# RPi_Peripheral_HAT.net
KiCad netlist of a schematic drawn in Altium Designer
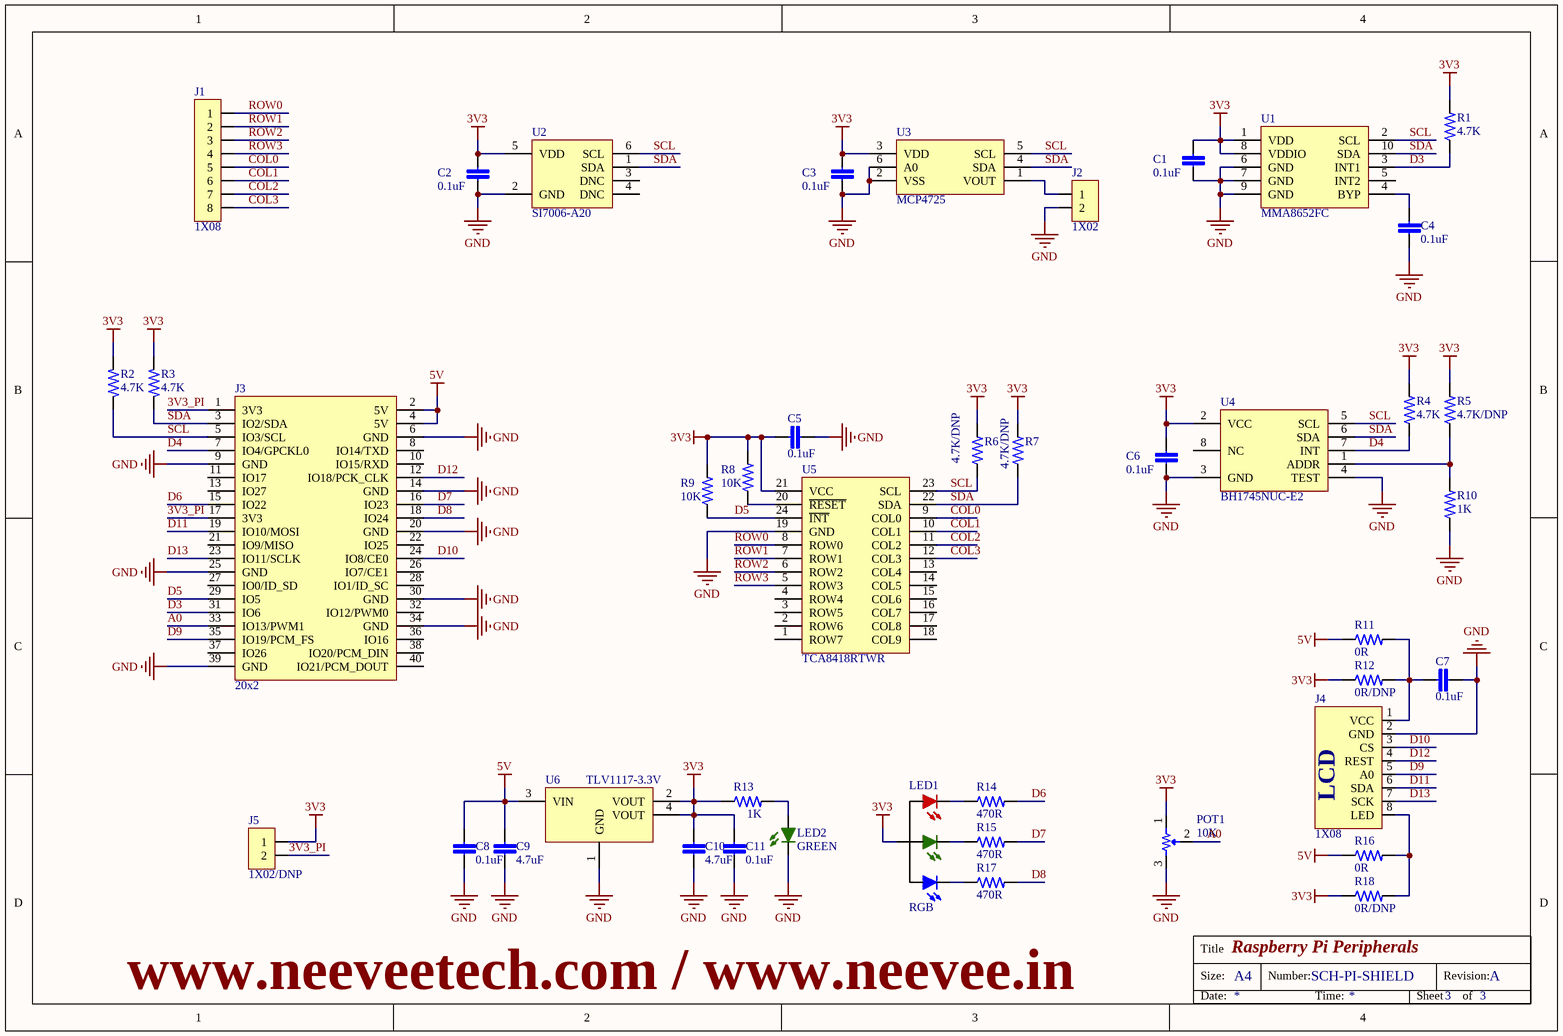
[diagram p0: RPi_Peripheral_HAT.SchDoc]

(export (version "E")
  (design (tool "Eeschema 10.0.6"))
  (components
    (comp (ref "C1")
      (value "0.1uF")
      (footprint "C0603")
      (description "Cap Ceramic 0.1uF 50V X7R 20% SMD 0603 125C T/R")
      (fields
        (field (name "MANUFACTURER") "KEMET")
        (field (name "MANUFACTURER PART NUMBER") "C0603C104M5RACTU")
      )
      (libsource (lib "Schematic_Library") (part "C0603_0.1uF"))
    )
    (comp (ref "C2")
      (value "0.1uF")
      (footprint "C0603")
      (description "Cap Ceramic 0.1uF 50V X7R 20% SMD 0603 125C T/R")
      (fields
        (field (name "MANUFACTURER") "KEMET")
        (field (name "MANUFACTURER PART NUMBER") "C0603C104M5RACTU")
      )
      (libsource (lib "Schematic_Library") (part "C0603_0.1uF"))
    )
    (comp (ref "C3")
      (value "0.1uF")
      (footprint "C0603")
      (description "Cap Ceramic 0.1uF 50V X7R 20% SMD 0603 125C T/R")
      (fields
        (field (name "MANUFACTURER") "KEMET")
        (field (name "MANUFACTURER PART NUMBER") "C0603C104M5RACTU")
      )
      (libsource (lib "Schematic_Library") (part "C0603_0.1uF"))
    )
    (comp (ref "C4")
      (value "0.1uF")
      (footprint "C0603")
      (description "Cap Ceramic 0.1uF 50V X7R 20% SMD 0603 125C T/R")
      (fields
        (field (name "MANUFACTURER") "KEMET")
        (field (name "MANUFACTURER PART NUMBER") "C0603C104M5RACTU")
      )
      (libsource (lib "") (part "C0603_0.1uF_2"))
    )
    (comp (ref "C5")
      (value "0.1uF")
      (footprint "C0603")
      (description "Cap Ceramic 0.1uF 50V X7R 20% SMD 0603 125C T/R")
      (fields
        (field (name "MANUFACTURER") "KEMET")
        (field (name "MANUFACTURER PART NUMBER") "C0603C104M5RACTU")
      )
      (libsource (lib "") (part "C0603_0.1uF_3"))
    )
    (comp (ref "C6")
      (value "0.1uF")
      (footprint "C0603")
      (description "Cap Ceramic 0.1uF 50V X7R 20% SMD 0603 125C T/R")
      (fields
        (field (name "MANUFACTURER") "KEMET")
        (field (name "MANUFACTURER PART NUMBER") "C0603C104M5RACTU")
      )
      (libsource (lib "Schematic_Library") (part "C0603_0.1uF"))
    )
    (comp (ref "C7")
      (value "0.1uF")
      (footprint "C0603")
      (description "Cap Ceramic 0.1uF 50V X7R 20% SMD 0603 125C T/R")
      (fields
        (field (name "MANUFACTURER") "KEMET")
        (field (name "MANUFACTURER PART NUMBER") "C0603C104M5RACTU")
      )
      (libsource (lib "Schematic_Library") (part "C0603_0.1uF"))
    )
    (comp (ref "C8")
      (value "0.1uF")
      (footprint "C0603")
      (description "Cap Ceramic 0.1uF 50V X7R 20% SMD 0603 125C T/R")
      (fields
        (field (name "MANUFACTURER") "KEMET")
        (field (name "MANUFACTURER PART NUMBER") "C0603C104M5RACTU")
      )
      (libsource (lib "") (part "C0603_0.1uF_1"))
    )
    (comp (ref "C9")
      (value "4.7uF")
      (footprint "C0603")
      (description "4.7µF ±10% 10V Ceramic Capacitor X6S 0603 (1608 Metric)")
      (fields
        (field (name "MANUFACTURER") "TDK")
        (field (name "MANUFACTURER PART NUMBER") "C1608X6S1A475K080AC")
      )
      (libsource (lib "Schematic_Library") (part "C0603_4.7uF_10V"))
    )
    (comp (ref "C10")
      (value "4.7uF")
      (footprint "C0603")
      (description "4.7µF ±10% 10V Ceramic Capacitor X6S 0603 (1608 Metric)")
      (fields
        (field (name "MANUFACTURER") "TDK")
        (field (name "MANUFACTURER PART NUMBER") "C1608X6S1A475K080AC")
      )
      (libsource (lib "Schematic_Library") (part "C0603_4.7uF_10V"))
    )
    (comp (ref "C11")
      (value "0.1uF")
      (footprint "C0603")
      (description "Cap Ceramic 0.1uF 50V X7R 20% SMD 0603 125C T/R")
      (fields
        (field (name "MANUFACTURER") "KEMET")
        (field (name "MANUFACTURER PART NUMBER") "C0603C104M5RACTU")
      )
      (libsource (lib "") (part "C0603_0.1uF_1"))
    )
    (comp (ref "J1")
      (value "1X08")
      (footprint "CON_1X08_2.54mm_male_TH")
      (description "Connector Header Through Hole 8 position 0.100\" (2.54mm)")
      (fields
        (field (name "MANUFACTURER") "Amphenol FCI")
        (field (name "MANUFACTURER PART NUMBER") "77311-818-08LF")
      )
      (libsource (lib "Schematic_Library") (part "CON_1X08_2.54mm_male_TH"))
    )
    (comp (ref "J2")
      (value "1X02")
      (footprint "CON_1X02_5MM")
      (description "Wire-To-Board Terminal Block, 5 mm, 2 Ways, 22 AWG, 14 AWG, 1.5 mm, Screw")
      (fields
        (field (name "MANUFACTURER") "Camden Electronics Boss")
        (field (name "MANUFACTURER PART NUMBER") "CTBP5000/2")
      )
      (libsource (lib "Schematic_Library") (part "CON_1X02_5mm"))
    )
    (comp (ref "J3")
      (value "20x2")
      (footprint "RPI_HEADER_2X20_FEMALE")
      (description "GPIO FEMALE HEADER RASPBERRY PI")
      (fields
        (field (name "MANUFACTURER") "Adafruit Industries")
        (field (name "MANUFACTURER PART NUMBER") "2222")
      )
      (libsource (lib "Schematic_Library") (part "RPI_HEADER_20X2_FEMALE"))
    )
    (comp (ref "J4")
      (value "1X08")
      (footprint "CON_1X08_2.54mm_Female_TH")
      (description "Board-To-Board Connector, 2.54 mm, 10 Contacts, Receptacle, 2212S Series, Through Hole, 1 Rows")
      (fields
        (field (name "MANUFACTURER") "Multicomp")
        (field (name "MANUFACTURER PART NUMBER") "2212S-10SG-85")
      )
      (libsource (lib "Schematic_Library") (part "1.44Inch_TFT_LCD_Con"))
    )
    (comp (ref "J5")
      (value "1X02/DNP")
      (footprint "CON_1X02_2.54mm_Male")
      (description "Connector Header Through Hole 2 position 0.100\" (2.54mm)")
      (fields
        (field (name "MANUFACTURER") "Amphenol FCI")
        (field (name "MANUFACTURER PART NUMBER") "77311-818-02LF")
      )
      (libsource (lib "Schematic_Library") (part "CON_1X02_2.54mm_Male"))
    )
    (comp (ref "LED1")
      (value "RGB")
      (footprint "PLCC4")
      (fields
        (field (name "MANUFACTURER") "Broadcom Avago")
        (field (name "MANUFACTURER PART NUMBER") "ASMB-MTB0-0A3A2")
      )
      (libsource (lib "Schematic_Library") (part "LED_RGB"))
    )
    (comp (ref "LED2")
      (value "GREEN")
      (footprint "LED_0805_GREEN")
      (description "KP-2012LCGCK -  LED, Low Power, Green, SMD, 0805, 2 mA, 1.9 V, 570 nm")
      (fields
        (field (name "MANUFACTURER") "Kingbright")
        (field (name "MANUFACTURER PART NUMBER") "KP-2012LCGCK")
      )
      (libsource (lib "Schematic_Library") (part "LED0805_GREEN"))
    )
    (comp (ref "POT1")
      (value "10K")
      (footprint "PTV09A_POTENTIOMETER")
      (fields
        (field (name "MANUFACTURER") "Bourns")
        (field (name "MANUFACTURER PART NUMBER") "PTV09A-4015U-B103")
        (field (name "TOLERANCE") "20%")
      )
      (libsource (lib "Schematic_Library") (part "PTV09A-4015U-B103"))
    )
    (comp (ref "R1")
      (value "4.7K")
      (footprint "R0603")
      (description "SMD Chip Resistor, 0603 [1608 Metric], 4.7 kohm, MCWR Series, 75 V, Thick Film, 100 mW")
      (fields
        (field (name "MANUFACTURER") "Multicomp")
        (field (name "MANUFACTURER PART NUMBER") "MCWR06X4701FTL")
      )
      (libsource (lib "Schematic_Library") (part "R0603_4.7K"))
    )
    (comp (ref "R2")
      (value "4.7K")
      (footprint "R0603")
      (description "SMD Chip Resistor, 0603 [1608 Metric], 4.7 kohm, MCWR Series, 75 V, Thick Film, 100 mW")
      (fields
        (field (name "MANUFACTURER") "Multicomp")
        (field (name "MANUFACTURER PART NUMBER") "MCWR06X4701FTL")
      )
      (libsource (lib "Schematic_Library") (part "R0603_4.7K"))
    )
    (comp (ref "R3")
      (value "4.7K")
      (footprint "R0603")
      (description "SMD Chip Resistor, 0603 [1608 Metric], 4.7 kohm, MCWR Series, 75 V, Thick Film, 100 mW")
      (fields
        (field (name "MANUFACTURER") "Multicomp")
        (field (name "MANUFACTURER PART NUMBER") "MCWR06X4701FTL")
      )
      (libsource (lib "Schematic_Library") (part "R0603_4.7K"))
    )
    (comp (ref "R4")
      (value "4.7K")
      (footprint "R0603")
      (description "SMD Chip Resistor, 0603 [1608 Metric], 4.7 kohm, MCWR Series, 75 V, Thick Film, 100 mW")
      (fields
        (field (name "MANUFACTURER") "Multicomp")
        (field (name "MANUFACTURER PART NUMBER") "MCWR06X4701FTL")
      )
      (libsource (lib "Schematic_Library") (part "R0603_4.7K"))
    )
    (comp (ref "R5")
      (value "4.7K/DNP")
      (footprint "R0603")
      (description "SMD Chip Resistor, 0603 [1608 Metric], 4.7 kohm, MCWR Series, 75 V, Thick Film, 100 mW (DNP)")
      (fields
        (field (name "MANUFACTURER") "Multicomp")
        (field (name "MANUFACTURER PART NUMBER") "MCWR06X4701FTL")
      )
      (libsource (lib "Schematic_Library") (part "R0603_4.7K/DNP"))
    )
    (comp (ref "R6")
      (value "4.7K/DNP")
      (footprint "R0603")
      (description "SMD Chip Resistor, 0603 [1608 Metric], 4.7 kohm, MCWR Series, 75 V, Thick Film, 100 mW (DNP)")
      (fields
        (field (name "MANUFACTURER") "Multicomp")
        (field (name "MANUFACTURER PART NUMBER") "MCWR06X4701FTL")
      )
      (libsource (lib "Schematic_Library") (part "R0603_4.7K/DNP"))
    )
    (comp (ref "R7")
      (value "4.7K/DNP")
      (footprint "R0603")
      (description "SMD Chip Resistor, 0603 [1608 Metric], 4.7 kohm, MCWR Series, 75 V, Thick Film, 100 mW (DNP)")
      (fields
        (field (name "MANUFACTURER") "Multicomp")
        (field (name "MANUFACTURER PART NUMBER") "MCWR06X4701FTL")
      )
      (libsource (lib "Schematic_Library") (part "R0603_4.7K/DNP"))
    )
    (comp (ref "R8")
      (value "10K")
      (footprint "R0603")
      (description "SMD Chip Resistor, 0603 [1608 Metric], 10 kohm, MCWR Series, 75 V, Thick Film, 100 mW")
      (fields
        (field (name "MANUFACTURER") "Multicomp")
        (field (name "MANUFACTURER PART NUMBER") "MCWR06X1002FTL")
      )
      (libsource (lib "Schematic_Library") (part "R0603_10K"))
    )
    (comp (ref "R9")
      (value "10K")
      (footprint "R0603")
      (description "SMD Chip Resistor, 0603 [1608 Metric], 10 kohm, MCWR Series, 75 V, Thick Film, 100 mW")
      (fields
        (field (name "MANUFACTURER") "Multicomp")
        (field (name "MANUFACTURER PART NUMBER") "MCWR06X1002FTL")
      )
      (libsource (lib "Schematic_Library") (part "R0603_10K"))
    )
    (comp (ref "R10")
      (value "1K")
      (footprint "R0603")
      (description "SMD Chip Resistor, 0603 [1608 Metric], 1 kohm, MCWR Series, 75 V, Thick Film, 100 mW")
      (fields
        (field (name "MANUFACTURER") "Multicomp")
        (field (name "MANUFACTURER PART NUMBER") "MCWR06X1001FTL")
      )
      (libsource (lib "Schematic_Library") (part "R0603_1K"))
    )
    (comp (ref "R11")
      (value "0R")
      (footprint "R0603")
      (description "SMD Chip Resistor, Jumper, 0603 [1608 Metric], 0 ohm, MCWR Series, 75 V, Thick Film, 100 mW")
      (fields
        (field (name "MANUFACTURER") "Multicomp")
        (field (name "MANUFACTURER PART NUMBER") "MCWR06X000PTL")
      )
      (libsource (lib "Schematic_Library") (part "R0603_0R"))
    )
    (comp (ref "R12")
      (value "0R/DNP")
      (footprint "R0603")
      (description "SMD Chip Resistor, Jumper, 0603 [1608 Metric], 0 ohm, MCWR Series, 75 V, Thick Film, 100 mW (DNP)")
      (fields
        (field (name "MANUFACTURER") "Multicomp")
        (field (name "MANUFACTURER PART NUMBER") "MCWR06X000PTL")
      )
      (libsource (lib "Schematic_Library") (part "R0603_0R_DNP"))
    )
    (comp (ref "R13")
      (value "1K")
      (footprint "R0603")
      (description "SMD Chip Resistor, 0603 [1608 Metric], 1 kohm, MCWR Series, 75 V, Thick Film, 100 mW")
      (fields
        (field (name "MANUFACTURER") "Multicomp")
        (field (name "MANUFACTURER PART NUMBER") "MCWR06X1001FTL")
      )
      (libsource (lib "Schematic_Library") (part "R0603_1K"))
    )
    (comp (ref "R14")
      (value "470R")
      (footprint "R0603")
      (description "SMD Chip Resistor, 0603 [1608 Metric], 470 ohm, MCWR Series, 75 V, Thick Film, 100 mW")
      (fields
        (field (name "MANUFACTURER") "Multicomp")
        (field (name "MANUFACTURER PART NUMBER") "MCWR06X4700FTL")
      )
      (libsource (lib "Schematic_Library") (part "R0603_470R"))
    )
    (comp (ref "R15")
      (value "470R")
      (footprint "R0603")
      (description "SMD Chip Resistor, 0603 [1608 Metric], 470 ohm, MCWR Series, 75 V, Thick Film, 100 mW")
      (fields
        (field (name "MANUFACTURER") "Multicomp")
        (field (name "MANUFACTURER PART NUMBER") "MCWR06X4700FTL")
      )
      (libsource (lib "Schematic_Library") (part "R0603_470R"))
    )
    (comp (ref "R16")
      (value "0R")
      (footprint "R0603")
      (description "SMD Chip Resistor, Jumper, 0603 [1608 Metric], 0 ohm, MCWR Series, 75 V, Thick Film, 100 mW")
      (fields
        (field (name "MANUFACTURER") "Multicomp")
        (field (name "MANUFACTURER PART NUMBER") "MCWR06X000PTL")
      )
      (libsource (lib "Schematic_Library") (part "R0603_0R"))
    )
    (comp (ref "R17")
      (value "470R")
      (footprint "R0603")
      (description "SMD Chip Resistor, 0603 [1608 Metric], 470 ohm, MCWR Series, 75 V, Thick Film, 100 mW")
      (fields
        (field (name "MANUFACTURER") "Multicomp")
        (field (name "MANUFACTURER PART NUMBER") "MCWR06X4700FTL")
      )
      (libsource (lib "Schematic_Library") (part "R0603_470R"))
    )
    (comp (ref "R18")
      (value "0R/DNP")
      (footprint "R0603")
      (description "SMD Chip Resistor, Jumper, 0603 [1608 Metric], 0 ohm, MCWR Series, 75 V, Thick Film, 100 mW (DNP)")
      (fields
        (field (name "MANUFACTURER") "Multicomp")
        (field (name "MANUFACTURER PART NUMBER") "MCWR06X000PTL")
      )
      (libsource (lib "Schematic_Library") (part "R0603_0R_DNP"))
    )
    (comp (ref "U1")
      (value "MMA8652FC")
      (footprint "DFN10")
      (description "Accelerometer X, Y, Z Axis ±2g, 4g, 8g 0.78Hz ~ 400Hz 10-DFN (2x2)")
      (fields
        (field (name "MANUFACTURER") "NXP Freescale")
        (field (name "MANUFACTURER PART NUMBER") "MMA8652FCR1")
      )
      (libsource (lib "Schematic_Library") (part "MMA8652FC"))
    )
    (comp (ref "U2")
      (value "SI7006-A20")
      (footprint "DFN6")
      (description "Humidity Temperature Sensor 0 ~ 100% RH I²C ±5% RH 18s Surface Mount")
      (fields
        (field (name "MANUFACTURER") "Silicon Labs")
        (field (name "MANUFACTURER PART NUMBER") "SI7006-A20-IM")
      )
      (libsource (lib "Schematic_Library") (part "SI7006-A20-IM"))
    )
    (comp (ref "U3")
      (value "MCP4725")
      (footprint "SOT23-6")
      (description "12 Bit Digital to Analog Converter 1 SOT-23-6")
      (fields
        (field (name "MANUFACTURER") "Microchip")
        (field (name "MANUFACTURER PART NUMBER") "MCP4725A2T-E/CH")
      )
      (libsource (lib "Schematic_Library") (part "MCP4725"))
    )
    (comp (ref "U4")
      (value "BH1745NUC-E2")
      (footprint "DFN8")
      (description "ROHM - BH1745NUC-E2 - Colour Sensor, 16 Bit, I2C, Serial Output, 2.3 V to 3.6 V, WSON-8")
      (fields (field (name "MANUFACTURER") "Rohm"))
      (libsource (lib "Schematic_Library") (part "BH1745NUC-E2"))
    )
    (comp (ref "U5")
      (value "TCA8418RTWR")
      (footprint "QFN24-0.5mm")
      (description "TCA8418 I2C Controlled Keypad Scan IC With Integrated ESD Protection")
      (fields (field (name "MANUFACTURER") "Texas Instruments"))
      (libsource (lib "Schematic_Library") (part "TCA8418RTWR"))
    )
    (comp (ref "U6")
      (value "TLV1117-3.3V")
      (footprint "SOT223")
      (description "Fixed LDO Voltage Regulator, 2V to 5.5V, 455mV Dropout, 3.3Vout, 1Aout, SOT-223-4")
      (fields
        (field (name "MANUFACTURER") "Texas Instruments")
        (field (name "MANUFACTURER PART NUMBER") "TLV1117LV33DCYR")
      )
      (libsource (lib "Schematic_Library") (part "TLV1117LV33"))
    )
  )
  (nets
    (net (code "1") (name "/3V3_PI") (class "Default")
      (node (ref "J3") (pin "1") (pinfunction "3V3_1") (pintype "passive"))
      (node (ref "J3") (pin "17") (pinfunction "3V3_17") (pintype "passive"))
      (node (ref "J5") (pin "2") (pinfunction "2_2") (pintype "passive"))
    )
    (net (code "2") (name "/A0") (class "Default")
      (node (ref "J3") (pin "33") (pinfunction "IO13/PWM1_33") (pintype "passive"))
      (node (ref "POT1") (pin "2") (pinfunction "2_2") (pintype "passive"))
    )
    (net (code "3") (name "/COL0") (class "Default")
      (node (ref "J1") (pin "5") (pinfunction "5_5") (pintype "passive"))
      (node (ref "U5") (pin "9") (pinfunction "COL0_9") (pintype "passive"))
    )
    (net (code "4") (name "/COL1") (class "Default")
      (node (ref "J1") (pin "6") (pinfunction "6_6") (pintype "passive"))
      (node (ref "U5") (pin "10") (pinfunction "COL1_10") (pintype "passive"))
    )
    (net (code "5") (name "/COL2") (class "Default")
      (node (ref "J1") (pin "7") (pinfunction "7_7") (pintype "passive"))
      (node (ref "U5") (pin "11") (pinfunction "COL2_11") (pintype "passive"))
    )
    (net (code "6") (name "/COL3") (class "Default")
      (node (ref "J1") (pin "8") (pinfunction "8_8") (pintype "passive"))
      (node (ref "U5") (pin "12") (pinfunction "COL3_12") (pintype "passive"))
    )
    (net (code "7") (name "/D3") (class "Default")
      (node (ref "J3") (pin "31") (pinfunction "IO6_31") (pintype "passive"))
      (node (ref "R1") (pin "1") (pinfunction "1_1") (pintype "passive"))
      (node (ref "U1") (pin "3") (pinfunction "INT1_3") (pintype "passive"))
    )
    (net (code "8") (name "/D4") (class "Default")
      (node (ref "J3") (pin "7") (pinfunction "IO4/GPCKL0_7") (pintype "passive"))
      (node (ref "R4") (pin "1") (pinfunction "1_1") (pintype "passive"))
      (node (ref "U4") (pin "7") (pinfunction "INT_7") (pintype "passive"))
    )
    (net (code "9") (name "/D5") (class "Default")
      (node (ref "J3") (pin "29") (pinfunction "IO5_29") (pintype "passive"))
      (node (ref "R9") (pin "1") (pinfunction "1_1") (pintype "passive"))
      (node (ref "U5") (pin "24") (pinfunction "~{INT}_24") (pintype "passive"))
    )
    (net (code "10") (name "/D6") (class "Default")
      (node (ref "J3") (pin "15") (pinfunction "IO22_15") (pintype "passive"))
      (node (ref "R14") (pin "2") (pinfunction "2_2") (pintype "passive"))
    )
    (net (code "11") (name "/D7") (class "Default")
      (node (ref "J3") (pin "16") (pinfunction "IO23_16") (pintype "passive"))
      (node (ref "R15") (pin "2") (pinfunction "2_2") (pintype "passive"))
    )
    (net (code "12") (name "/D8") (class "Default")
      (node (ref "J3") (pin "18") (pinfunction "IO24_18") (pintype "passive"))
      (node (ref "R17") (pin "2") (pinfunction "2_2") (pintype "passive"))
    )
    (net (code "13") (name "/D9") (class "Default")
      (node (ref "J3") (pin "35") (pinfunction "IO19/PCM_FS_35") (pintype "passive"))
      (node (ref "J4") (pin "5") (pinfunction "A0_5") (pintype "passive"))
    )
    (net (code "14") (name "/D10") (class "Default")
      (node (ref "J3") (pin "24") (pinfunction "IO8/CE0_24") (pintype "passive"))
      (node (ref "J4") (pin "3") (pinfunction "CS_3") (pintype "passive"))
    )
    (net (code "15") (name "/D11") (class "Default")
      (node (ref "J3") (pin "19") (pinfunction "IO10/MOSI_19") (pintype "passive"))
      (node (ref "J4") (pin "6") (pinfunction "SDA_6") (pintype "passive"))
    )
    (net (code "16") (name "/D12") (class "Default")
      (node (ref "J3") (pin "12") (pinfunction "IO18/PCK_CLK_12") (pintype "passive"))
      (node (ref "J4") (pin "4") (pinfunction "REST_4") (pintype "passive"))
    )
    (net (code "17") (name "/D13") (class "Default")
      (node (ref "J3") (pin "23") (pinfunction "IO11/SCLK_23") (pintype "passive"))
      (node (ref "J4") (pin "7") (pinfunction "SCK_7") (pintype "passive"))
    )
    (net (code "18") (name "/ROW0") (class "Default")
      (node (ref "J1") (pin "1") (pinfunction "1_1") (pintype "passive"))
      (node (ref "U5") (pin "8") (pinfunction "ROW0_8") (pintype "passive"))
    )
    (net (code "19") (name "/ROW1") (class "Default")
      (node (ref "J1") (pin "2") (pinfunction "2_2") (pintype "passive"))
      (node (ref "U5") (pin "7") (pinfunction "ROW1_7") (pintype "passive"))
    )
    (net (code "20") (name "/ROW2") (class "Default")
      (node (ref "J1") (pin "3") (pinfunction "3_3") (pintype "passive"))
      (node (ref "U5") (pin "6") (pinfunction "ROW2_6") (pintype "passive"))
    )
    (net (code "21") (name "/ROW3") (class "Default")
      (node (ref "J1") (pin "4") (pinfunction "4_4") (pintype "passive"))
      (node (ref "U5") (pin "5") (pinfunction "ROW3_5") (pintype "passive"))
    )
    (net (code "22") (name "/SCL") (class "Default")
      (node (ref "J3") (pin "5") (pinfunction "IO3/SCL_5") (pintype "passive"))
      (node (ref "R2") (pin "1") (pinfunction "1_1") (pintype "passive"))
      (node (ref "R6") (pin "1") (pinfunction "1_1") (pintype "passive"))
      (node (ref "U1") (pin "2") (pinfunction "SCL_2") (pintype "passive"))
      (node (ref "U2") (pin "6") (pinfunction "SCL_6") (pintype "passive"))
      (node (ref "U3") (pin "5") (pinfunction "SCL_5") (pintype "passive"))
      (node (ref "U4") (pin "5") (pinfunction "SCL_5") (pintype "passive"))
      (node (ref "U5") (pin "23") (pinfunction "SCL_23") (pintype "passive"))
    )
    (net (code "23") (name "/SDA") (class "Default")
      (node (ref "J3") (pin "3") (pinfunction "IO2/SDA_3") (pintype "passive"))
      (node (ref "R3") (pin "1") (pinfunction "1_1") (pintype "passive"))
      (node (ref "R7") (pin "1") (pinfunction "1_1") (pintype "passive"))
      (node (ref "U1") (pin "10") (pinfunction "SDA_10") (pintype "passive"))
      (node (ref "U2") (pin "1") (pinfunction "SDA_1") (pintype "passive"))
      (node (ref "U3") (pin "4") (pinfunction "SDA_4") (pintype "passive"))
      (node (ref "U4") (pin "6") (pinfunction "SDA_6") (pintype "passive"))
      (node (ref "U5") (pin "22") (pinfunction "SDA_22") (pintype "passive"))
    )
    (net (code "24") (name "3V3") (class "Default")
      (node (ref "C1") (pin "2") (pinfunction "2_2") (pintype "passive"))
      (node (ref "C10") (pin "1") (pinfunction "1_1") (pintype "passive"))
      (node (ref "C11") (pin "2") (pinfunction "2_2") (pintype "passive"))
      (node (ref "C2") (pin "2") (pinfunction "2_2") (pintype "passive"))
      (node (ref "C3") (pin "2") (pinfunction "2_2") (pintype "passive"))
      (node (ref "C5") (pin "2") (pinfunction "2_2") (pintype "passive"))
      (node (ref "C6") (pin "2") (pinfunction "2_2") (pintype "passive"))
      (node (ref "J5") (pin "1") (pinfunction "1_1") (pintype "passive"))
      (node (ref "LED1") (pin "1") (pinfunction "CA_1") (pintype "passive"))
      (node (ref "POT1") (pin "1") (pinfunction "1_1") (pintype "passive"))
      (node (ref "R1") (pin "2") (pinfunction "2_2") (pintype "passive"))
      (node (ref "R12") (pin "1") (pinfunction "1_1") (pintype "passive"))
      (node (ref "R13") (pin "1") (pinfunction "1_1") (pintype "passive"))
      (node (ref "R18") (pin "1") (pinfunction "1_1") (pintype "passive"))
      (node (ref "R2") (pin "2") (pinfunction "2_2") (pintype "passive"))
      (node (ref "R3") (pin "2") (pinfunction "2_2") (pintype "passive"))
      (node (ref "R4") (pin "2") (pinfunction "2_2") (pintype "passive"))
      (node (ref "R5") (pin "2") (pinfunction "2_2") (pintype "passive"))
      (node (ref "R6") (pin "2") (pinfunction "2_2") (pintype "passive"))
      (node (ref "R7") (pin "2") (pinfunction "2_2") (pintype "passive"))
      (node (ref "R8") (pin "2") (pinfunction "2_2") (pintype "passive"))
      (node (ref "R9") (pin "2") (pinfunction "2_2") (pintype "passive"))
      (node (ref "U1") (pin "1") (pinfunction "VDD_1") (pintype "passive"))
      (node (ref "U1") (pin "8") (pinfunction "VDDIO_8") (pintype "passive"))
      (node (ref "U2") (pin "5") (pinfunction "VDD_5") (pintype "passive"))
      (node (ref "U3") (pin "3") (pinfunction "VDD_3") (pintype "passive"))
      (node (ref "U4") (pin "2") (pinfunction "VCC_2") (pintype "passive"))
      (node (ref "U5") (pin "21") (pinfunction "VCC_21") (pintype "passive"))
      (node (ref "U6") (pin "2") (pinfunction "VOUT_2") (pintype "passive"))
      (node (ref "U6") (pin "4") (pinfunction "VOUT_4") (pintype "passive"))
    )
    (net (code "25") (name "5V") (class "Default")
      (node (ref "C8") (pin "2") (pinfunction "2_2") (pintype "passive"))
      (node (ref "C9") (pin "1") (pinfunction "1_1") (pintype "passive"))
      (node (ref "J3") (pin "2") (pinfunction "5V_2") (pintype "passive"))
      (node (ref "J3") (pin "4") (pinfunction "5V_4") (pintype "passive"))
      (node (ref "R11") (pin "1") (pinfunction "1_1") (pintype "passive"))
      (node (ref "R16") (pin "1") (pinfunction "1_1") (pintype "passive"))
      (node (ref "U6") (pin "3") (pinfunction "VIN_3") (pintype "passive"))
    )
    (net (code "26") (name "GND") (class "Default")
      (node (ref "C1") (pin "1") (pinfunction "1_1") (pintype "passive"))
      (node (ref "C10") (pin "2") (pinfunction "2_2") (pintype "passive"))
      (node (ref "C11") (pin "1") (pinfunction "1_1") (pintype "passive"))
      (node (ref "C2") (pin "1") (pinfunction "1_1") (pintype "passive"))
      (node (ref "C3") (pin "1") (pinfunction "1_1") (pintype "passive"))
      (node (ref "C4") (pin "2") (pinfunction "2_2") (pintype "passive"))
      (node (ref "C5") (pin "1") (pinfunction "1_1") (pintype "passive"))
      (node (ref "C6") (pin "1") (pinfunction "1_1") (pintype "passive"))
      (node (ref "C7") (pin "2") (pinfunction "2_2") (pintype "passive"))
      (node (ref "C8") (pin "1") (pinfunction "1_1") (pintype "passive"))
      (node (ref "C9") (pin "2") (pinfunction "2_2") (pintype "passive"))
      (node (ref "J2") (pin "2") (pinfunction "2_2") (pintype "passive"))
      (node (ref "J3") (pin "14") (pinfunction "GND_14") (pintype "passive"))
      (node (ref "J3") (pin "20") (pinfunction "GND_20") (pintype "passive"))
      (node (ref "J3") (pin "25") (pinfunction "GND_25") (pintype "passive"))
      (node (ref "J3") (pin "30") (pinfunction "GND_30") (pintype "passive"))
      (node (ref "J3") (pin "34") (pinfunction "GND_34") (pintype "passive"))
      (node (ref "J3") (pin "39") (pinfunction "GND_39") (pintype "passive"))
      (node (ref "J3") (pin "6") (pinfunction "GND_6") (pintype "passive"))
      (node (ref "J3") (pin "9") (pinfunction "GND_9") (pintype "passive"))
      (node (ref "J4") (pin "2") (pinfunction "GND_2") (pintype "passive"))
      (node (ref "LED2") (pin "C") (pinfunction "C_C") (pintype "passive"))
      (node (ref "POT1") (pin "3") (pinfunction "3_3") (pintype "passive"))
      (node (ref "R10") (pin "1") (pinfunction "1_1") (pintype "passive"))
      (node (ref "U1") (pin "6") (pinfunction "GND_6") (pintype "passive"))
      (node (ref "U1") (pin "7") (pinfunction "GND_7") (pintype "passive"))
      (node (ref "U1") (pin "9") (pinfunction "GND_9") (pintype "passive"))
      (node (ref "U2") (pin "2") (pinfunction "GND_2") (pintype "passive"))
      (node (ref "U3") (pin "2") (pinfunction "VSS_2") (pintype "passive"))
      (node (ref "U3") (pin "6") (pinfunction "A0_6") (pintype "passive"))
      (node (ref "U4") (pin "3") (pinfunction "GND_3") (pintype "passive"))
      (node (ref "U4") (pin "4") (pinfunction "TEST_4") (pintype "passive"))
      (node (ref "U5") (pin "19") (pinfunction "GND_19") (pintype "passive"))
      (node (ref "U6") (pin "1") (pinfunction "GND_1") (pintype "passive"))
    )
    (net (code "27") (name "Net-(J4-LED)") (class "Default")
      (node (ref "J4") (pin "8") (pinfunction "LED_8") (pintype "passive"))
      (node (ref "R16") (pin "2") (pinfunction "2_2") (pintype "passive"))
      (node (ref "R18") (pin "2") (pinfunction "2_2") (pintype "passive"))
    )
    (net (code "28") (name "Net-(J4-VCC)") (class "Default")
      (node (ref "C7") (pin "1") (pinfunction "1_1") (pintype "passive"))
      (node (ref "J4") (pin "1") (pinfunction "VCC_1") (pintype "passive"))
      (node (ref "R11") (pin "2") (pinfunction "2_2") (pintype "passive"))
      (node (ref "R12") (pin "2") (pinfunction "2_2") (pintype "passive"))
    )
    (net (code "29") (name "Net-(LED1-BLUE)") (class "Default")
      (node (ref "LED1") (pin "2") (pinfunction "BLUE_2") (pintype "passive"))
      (node (ref "R17") (pin "1") (pinfunction "1_1") (pintype "passive"))
    )
    (net (code "30") (name "Net-(LED1-GREEN)") (class "Default")
      (node (ref "LED1") (pin "3") (pinfunction "GREEN_3") (pintype "passive"))
      (node (ref "R15") (pin "1") (pinfunction "1_1") (pintype "passive"))
    )
    (net (code "31") (name "Net-(LED1-RED)") (class "Default")
      (node (ref "LED1") (pin "4") (pinfunction "RED_4") (pintype "passive"))
      (node (ref "R14") (pin "1") (pinfunction "1_1") (pintype "passive"))
    )
    (net (code "32") (name "Net-(LED2-PadA)") (class "Default")
      (node (ref "LED2") (pin "A") (pinfunction "A_A") (pintype "passive"))
      (node (ref "R13") (pin "2") (pinfunction "2_2") (pintype "passive"))
    )
    (net (code "33") (name "Net-(U1-BYP)") (class "Default")
      (node (ref "C4") (pin "1") (pinfunction "1_1") (pintype "passive"))
      (node (ref "U1") (pin "4") (pinfunction "BYP_4") (pintype "passive"))
    )
    (net (code "34") (name "Net-(U3-VOUT)") (class "Default")
      (node (ref "J2") (pin "1") (pinfunction "1_1") (pintype "passive"))
      (node (ref "U3") (pin "1") (pinfunction "VOUT_1") (pintype "passive"))
    )
    (net (code "35") (name "Net-(U4-ADDR)") (class "Default")
      (node (ref "R10") (pin "2") (pinfunction "2_2") (pintype "passive"))
      (node (ref "R5") (pin "1") (pinfunction "1_1") (pintype "passive"))
      (node (ref "U4") (pin "1") (pinfunction "ADDR_1") (pintype "passive"))
    )
    (net (code "36") (name "Net-(U5-~{RESET})") (class "Default")
      (node (ref "R8") (pin "1") (pinfunction "1_1") (pintype "passive"))
      (node (ref "U5") (pin "20") (pinfunction "~{RESET}_20") (pintype "passive"))
    )
    (net (code "37") (name "unconnected-(J3-IO0{slash}ID_SD-Pad27)") (class "Default")
      (node (ref "J3") (pin "27") (pinfunction "IO0/ID_SD_27") (pintype "passive"))
    )
    (net (code "38") (name "unconnected-(J3-IO1{slash}ID_SC-Pad28)") (class "Default")
      (node (ref "J3") (pin "28") (pinfunction "IO1/ID_SC_28") (pintype "passive"))
    )
    (net (code "39") (name "unconnected-(J3-IO7{slash}CE1-Pad26)") (class "Default")
      (node (ref "J3") (pin "26") (pinfunction "IO7/CE1_26") (pintype "passive"))
    )
    (net (code "40") (name "unconnected-(J3-IO9{slash}MISO-Pad21)") (class "Default")
      (node (ref "J3") (pin "21") (pinfunction "IO9/MISO_21") (pintype "passive"))
    )
    (net (code "41") (name "unconnected-(J3-IO12{slash}PWM0-Pad32)") (class "Default")
      (node (ref "J3") (pin "32") (pinfunction "IO12/PWM0_32") (pintype "passive"))
    )
    (net (code "42") (name "unconnected-(J3-IO14{slash}TXD-Pad8)") (class "Default")
      (node (ref "J3") (pin "8") (pinfunction "IO14/TXD_8") (pintype "passive"))
    )
    (net (code "43") (name "unconnected-(J3-IO15{slash}RXD-Pad10)") (class "Default")
      (node (ref "J3") (pin "10") (pinfunction "IO15/RXD_10") (pintype "passive"))
    )
    (net (code "44") (name "unconnected-(J3-IO16-Pad36)") (class "Default")
      (node (ref "J3") (pin "36") (pinfunction "IO16_36") (pintype "passive"))
    )
    (net (code "45") (name "unconnected-(J3-IO17-Pad11)") (class "Default")
      (node (ref "J3") (pin "11") (pinfunction "IO17_11") (pintype "passive"))
    )
    (net (code "46") (name "unconnected-(J3-IO20{slash}PCM_DIN-Pad38)") (class "Default")
      (node (ref "J3") (pin "38") (pinfunction "IO20/PCM_DIN_38") (pintype "passive"))
    )
    (net (code "47") (name "unconnected-(J3-IO21{slash}PCM_DOUT-Pad40)") (class "Default")
      (node (ref "J3") (pin "40") (pinfunction "IO21/PCM_DOUT_40") (pintype "passive"))
    )
    (net (code "48") (name "unconnected-(J3-IO25-Pad22)") (class "Default")
      (node (ref "J3") (pin "22") (pinfunction "IO25_22") (pintype "passive"))
    )
    (net (code "49") (name "unconnected-(J3-IO26-Pad37)") (class "Default")
      (node (ref "J3") (pin "37") (pinfunction "IO26_37") (pintype "passive"))
    )
    (net (code "50") (name "unconnected-(J3-IO27-Pad13)") (class "Default")
      (node (ref "J3") (pin "13") (pinfunction "IO27_13") (pintype "passive"))
    )
    (net (code "51") (name "unconnected-(U1-INT2-Pad5)") (class "Default")
      (node (ref "U1") (pin "5") (pinfunction "INT2_5") (pintype "passive"))
    )
    (net (code "52") (name "unconnected-(U2-DNC-Pad3)") (class "Default")
      (node (ref "U2") (pin "3") (pinfunction "DNC_3") (pintype "passive"))
    )
    (net (code "53") (name "unconnected-(U2-DNC-Pad4)") (class "Default")
      (node (ref "U2") (pin "4") (pinfunction "DNC_4") (pintype "passive"))
    )
    (net (code "54") (name "unconnected-(U4-NC-Pad8)") (class "Default")
      (node (ref "U4") (pin "8") (pinfunction "NC_8") (pintype "passive"))
    )
    (net (code "55") (name "unconnected-(U5-COL4-Pad13)") (class "Default")
      (node (ref "U5") (pin "13") (pinfunction "COL4_13") (pintype "passive"))
    )
    (net (code "56") (name "unconnected-(U5-COL5-Pad14)") (class "Default")
      (node (ref "U5") (pin "14") (pinfunction "COL5_14") (pintype "passive"))
    )
    (net (code "57") (name "unconnected-(U5-COL6-Pad15)") (class "Default")
      (node (ref "U5") (pin "15") (pinfunction "COL6_15") (pintype "passive"))
    )
    (net (code "58") (name "unconnected-(U5-COL7-Pad16)") (class "Default")
      (node (ref "U5") (pin "16") (pinfunction "COL7_16") (pintype "passive"))
    )
    (net (code "59") (name "unconnected-(U5-COL8-Pad17)") (class "Default")
      (node (ref "U5") (pin "17") (pinfunction "COL8_17") (pintype "passive"))
    )
    (net (code "60") (name "unconnected-(U5-COL9-Pad18)") (class "Default")
      (node (ref "U5") (pin "18") (pinfunction "COL9_18") (pintype "passive"))
    )
    (net (code "61") (name "unconnected-(U5-ROW4-Pad4)") (class "Default")
      (node (ref "U5") (pin "4") (pinfunction "ROW4_4") (pintype "passive"))
    )
    (net (code "62") (name "unconnected-(U5-ROW5-Pad3)") (class "Default")
      (node (ref "U5") (pin "3") (pinfunction "ROW5_3") (pintype "passive"))
    )
    (net (code "63") (name "unconnected-(U5-ROW6-Pad2)") (class "Default")
      (node (ref "U5") (pin "2") (pinfunction "ROW6_2") (pintype "passive"))
    )
    (net (code "64") (name "unconnected-(U5-ROW7-Pad1)") (class "Default")
      (node (ref "U5") (pin "1") (pinfunction "ROW7_1") (pintype "passive"))
    )
  )
)
